# ETRX_Shield.net
KiCad netlist of a schematic drawn in Altium Designer
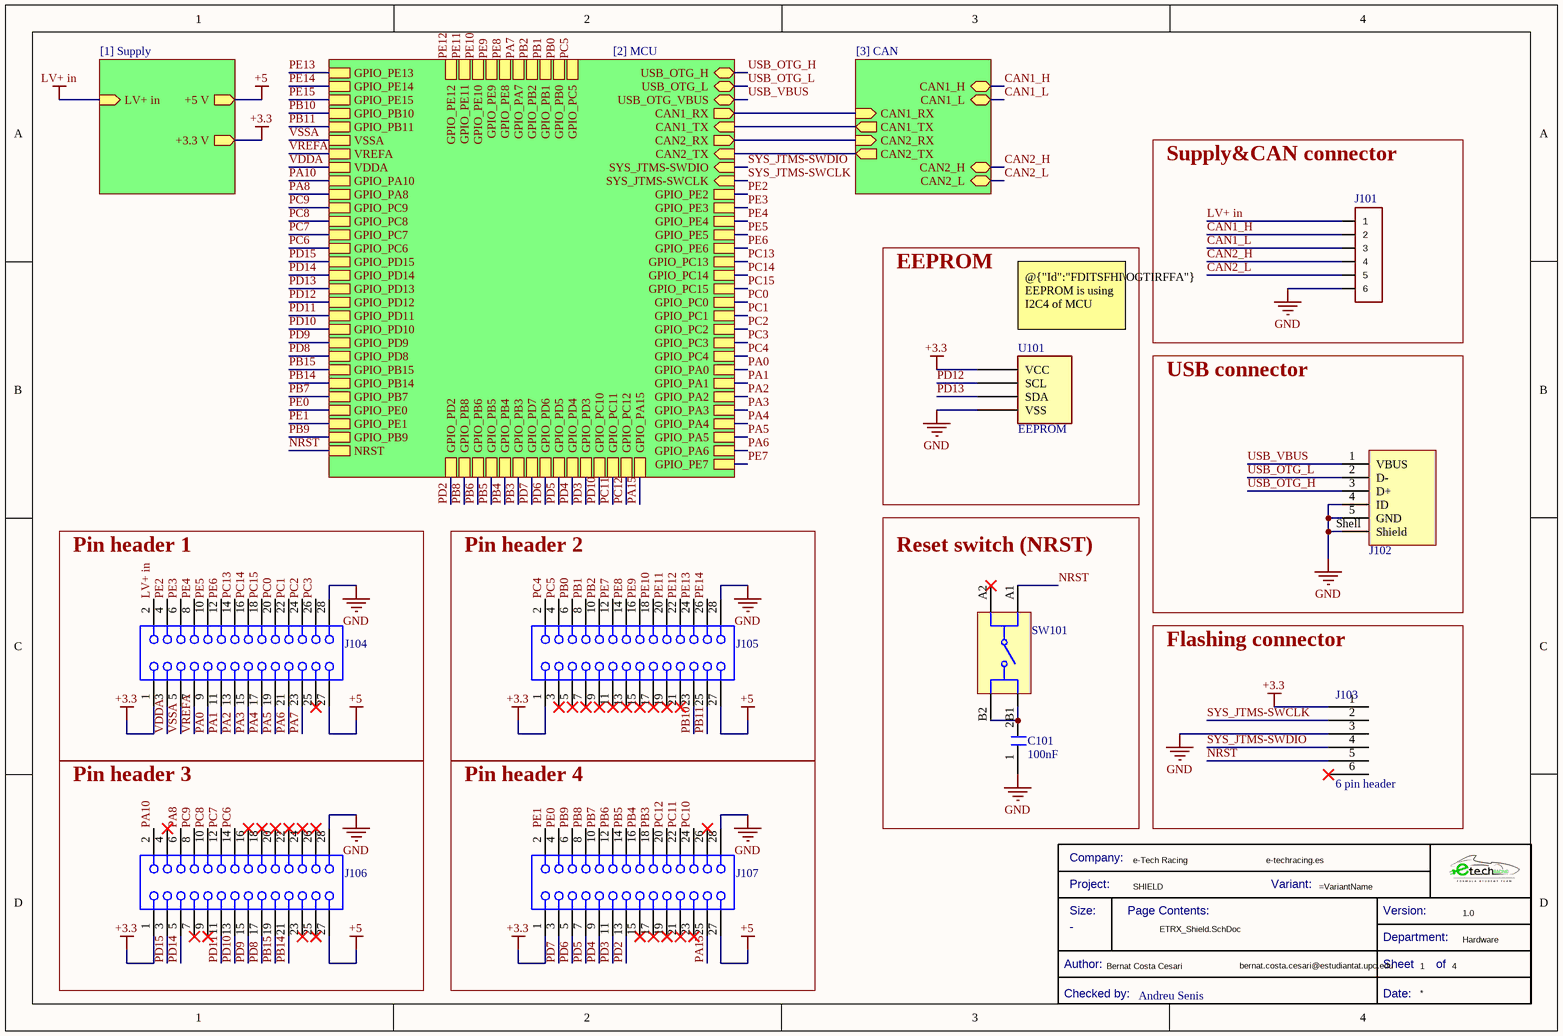
[diagram p0: ETRX_Shield.SchDoc]

(export (version "E")
  (design (tool "Eeschema 10.0.6"))
  (components
    (comp (ref "*")
      (value "Title Block_template")
      (description "Standard Title Block")
      (fields
        (field (name "SIZE") "-")
        (field (name ".CREATOR") "GP")
        (field (name ".PCBCHECK") "GP")
        (field (name ".SCHCHECK") "GP")
      )
      (libsource (lib "e-Tech_Racing") (part "Title Block_template"))
    )
    (comp (ref "C101")
      (value "885012208058")
      (footprint "C1206FNPC-RW")
      (description "Cap Cer 0.1UF 25V X7R 1206")
      (fields
        (field (name "MANUFACTURER") "Wurth Electronics")
        (field (name "TOLERANCE") "10%")
        (field (name "CAPACITANCE") "100nF")
        (field (name ".CREATOR") "DO")
      )
      (libsource (lib "Passives") (part "C100n-25V-1206FNPC-X7R"))
    )
    (comp (ref "J101")
      (value "LEMO Connector    6 pin EXG.0B.306.HLN Elbow receptacle for printed circuit (solder mount), Female Contact Drawing Rev. 00 Source: http://www.lemo.com/catalog/ROW/UK_English/unipole_multipole.pdf")
      (footprint "EXG.0B.306.HLN")
      (fields (field (name "MPN") "EXG.0B.306.HLN"))
      (libsource (lib "LEMO-EXG.0B.306.HLN") (part "EXG.0B.306.HLN"))
    )
    (comp (ref "J102")
      (value "629105136821")
      (footprint "629105136821")
      (description "WR-COM Micro USB 2.0 SMT Type B Horizontal 5 Contacts")
      (fields (field (name "MANUFACTURER") "Wurth Elektronik"))
      (libsource (lib "WR-USB") (part "629105136821"))
    )
    (comp (ref "J103") (value "6 pin header") (libsource (lib "CAN Transceiver") (part "6 pin header")))
    (comp (ref "J104")
      (value "62202821821")
      (footprint "62202821821")
      (description "WR-PHD Socket Header, THT, Vertical, pitch 1.27mm, 2 Row, 28P")
      (fields (field (name "MANUFACTURER") "Wurth Elektronik"))
      (libsource (lib "Altium_WR-PHD (rev22b)") (part "62202821821"))
    )
    (comp (ref "J105")
      (value "62202821821")
      (footprint "62202821821")
      (description "WR-PHD Socket Header, THT, Vertical, pitch 1.27mm, 2 Row, 28P")
      (fields (field (name "MANUFACTURER") "Wurth Elektronik"))
      (libsource (lib "Altium_WR-PHD (rev22b)") (part "62202821821"))
    )
    (comp (ref "J106")
      (value "62202821821")
      (footprint "62202821821")
      (description "WR-PHD Socket Header, THT, Vertical, pitch 1.27mm, 2 Row, 28P")
      (fields (field (name "MANUFACTURER") "Wurth Elektronik"))
      (libsource (lib "Altium_WR-PHD (rev22b)") (part "62202821821"))
    )
    (comp (ref "J107")
      (value "62202821821")
      (footprint "62202821821")
      (description "WR-PHD Socket Header, THT, Vertical, pitch 1.27mm, 2 Row, 28P")
      (fields (field (name "MANUFACTURER") "Wurth Elektronik"))
      (libsource (lib "Altium_WR-PHD (rev22b)") (part "62202821821"))
    )
    (comp (ref "SW101")
      (value "430773034825")
      (footprint "WS-TASV_L6W6H3.4_4307x30348xx")
      (description "WS-TASV J-Hook SMT Hermetic Tact Switch, L6 x W6 x H3.4mm, 250g, SPST-NO, 12V, 50mA")
      (fields (field (name "MANUFACTURER") "Wurth Elektronik"))
      (libsource (lib "Altium_WS-SW bo") (part "430773034825"))
    )
    (comp (ref "U101") (value "EEPROM") (libsource (lib "CAN Transceiver") (part "I2C_EEPROM")))
  )
  (nets
    (net (code "1") (name "+3.3") (class "Default")
      (node (ref "J103") (pin "1") (pinfunction "1_1") (pintype "passive"))
      (node (ref "J104") (pin "1") (pinfunction "1_1") (pintype "passive"))
      (node (ref "J105") (pin "1") (pinfunction "1_1") (pintype "passive"))
      (node (ref "J106") (pin "1") (pinfunction "1_1") (pintype "passive"))
      (node (ref "J107") (pin "1") (pinfunction "1_1") (pintype "passive"))
      (node (ref "U101") (pin "1") (pinfunction "VCC_1") (pintype "passive"))
    )
    (net (code "2") (name "+5") (class "Default")
      (node (ref "J104") (pin "27") (pinfunction "27_27") (pintype "passive"))
      (node (ref "J105") (pin "27") (pinfunction "27_27") (pintype "passive"))
      (node (ref "J106") (pin "27") (pinfunction "27_27") (pintype "passive"))
      (node (ref "J107") (pin "27") (pinfunction "27_27") (pintype "passive"))
    )
    (net (code "3") (name "/CAN1_H") (class "Default")
      (node (ref "J101") (pin "2") (pinfunction "2_2") (pintype "passive"))
    )
    (net (code "4") (name "/CAN1_L") (class "Default")
      (node (ref "J101") (pin "3") (pinfunction "3_3") (pintype "passive"))
    )
    (net (code "7") (name "/CAN2_H") (class "Default")
      (node (ref "J101") (pin "4") (pinfunction "4_4") (pintype "passive"))
    )
    (net (code "8") (name "/CAN2_L") (class "Default")
      (node (ref "J101") (pin "5") (pinfunction "5_5") (pintype "passive"))
    )
    (net (code "11") (name "/NRST") (class "Default")
      (node (ref "J103") (pin "5") (pinfunction "5_5") (pintype "passive"))
      (node (ref "SW101") (pin "A1") (pinfunction "A1_A1") (pintype "passive"))
    )
    (net (code "12") (name "/PA0") (class "Default")
      (node (ref "J104") (pin "9") (pinfunction "9_9") (pintype "passive"))
    )
    (net (code "13") (name "/PA1") (class "Default")
      (node (ref "J104") (pin "11") (pinfunction "11_11") (pintype "passive"))
    )
    (net (code "14") (name "/PA2") (class "Default")
      (node (ref "J104") (pin "13") (pinfunction "13_13") (pintype "passive"))
    )
    (net (code "15") (name "/PA3") (class "Default")
      (node (ref "J104") (pin "15") (pinfunction "15_15") (pintype "passive"))
    )
    (net (code "16") (name "/PA4") (class "Default")
      (node (ref "J104") (pin "17") (pinfunction "17_17") (pintype "passive"))
    )
    (net (code "17") (name "/PA5") (class "Default")
      (node (ref "J104") (pin "19") (pinfunction "19_19") (pintype "passive"))
    )
    (net (code "18") (name "/PA6") (class "Default")
      (node (ref "J104") (pin "21") (pinfunction "21_21") (pintype "passive"))
    )
    (net (code "19") (name "/PA7") (class "Default")
      (node (ref "J104") (pin "23") (pinfunction "23_23") (pintype "passive"))
    )
    (net (code "20") (name "/PA8") (class "Default")
      (node (ref "J106") (pin "6") (pinfunction "6_6") (pintype "passive"))
    )
    (net (code "21") (name "/PA10") (class "Default")
      (node (ref "J106") (pin "2") (pinfunction "2_2") (pintype "passive"))
    )
    (net (code "22") (name "/PA15") (class "Default")
      (node (ref "J107") (pin "25") (pinfunction "25_25") (pintype "passive"))
    )
    (net (code "23") (name "/PB0") (class "Default")
      (node (ref "J105") (pin "6") (pinfunction "6_6") (pintype "passive"))
    )
    (net (code "24") (name "/PB1") (class "Default")
      (node (ref "J105") (pin "8") (pinfunction "8_8") (pintype "passive"))
    )
    (net (code "25") (name "/PB2") (class "Default")
      (node (ref "J105") (pin "10") (pinfunction "10_10") (pintype "passive"))
    )
    (net (code "26") (name "/PB3") (class "Default")
      (node (ref "J107") (pin "18") (pinfunction "18_18") (pintype "passive"))
    )
    (net (code "27") (name "/PB4") (class "Default")
      (node (ref "J107") (pin "16") (pinfunction "16_16") (pintype "passive"))
    )
    (net (code "28") (name "/PB5") (class "Default")
      (node (ref "J107") (pin "14") (pinfunction "14_14") (pintype "passive"))
    )
    (net (code "29") (name "/PB6") (class "Default")
      (node (ref "J107") (pin "12") (pinfunction "12_12") (pintype "passive"))
    )
    (net (code "30") (name "/PB7") (class "Default")
      (node (ref "J107") (pin "10") (pinfunction "10_10") (pintype "passive"))
    )
    (net (code "31") (name "/PB8") (class "Default")
      (node (ref "J107") (pin "8") (pinfunction "8_8") (pintype "passive"))
    )
    (net (code "32") (name "/PB9") (class "Default")
      (node (ref "J107") (pin "6") (pinfunction "6_6") (pintype "passive"))
    )
    (net (code "33") (name "/PB10") (class "Default")
      (node (ref "J105") (pin "23") (pinfunction "23_23") (pintype "passive"))
    )
    (net (code "34") (name "/PB11") (class "Default")
      (node (ref "J105") (pin "25") (pinfunction "25_25") (pintype "passive"))
    )
    (net (code "35") (name "/PB14") (class "Default")
      (node (ref "J106") (pin "21") (pinfunction "21_21") (pintype "passive"))
    )
    (net (code "36") (name "/PB15") (class "Default")
      (node (ref "J106") (pin "19") (pinfunction "19_19") (pintype "passive"))
    )
    (net (code "37") (name "/PC0") (class "Default")
      (node (ref "J104") (pin "20") (pinfunction "20_20") (pintype "passive"))
    )
    (net (code "38") (name "/PC1") (class "Default")
      (node (ref "J104") (pin "22") (pinfunction "22_22") (pintype "passive"))
    )
    (net (code "39") (name "/PC2") (class "Default")
      (node (ref "J104") (pin "24") (pinfunction "24_24") (pintype "passive"))
    )
    (net (code "40") (name "/PC3") (class "Default")
      (node (ref "J104") (pin "26") (pinfunction "26_26") (pintype "passive"))
    )
    (net (code "41") (name "/PC4") (class "Default")
      (node (ref "J105") (pin "2") (pinfunction "2_2") (pintype "passive"))
    )
    (net (code "42") (name "/PC5") (class "Default")
      (node (ref "J105") (pin "4") (pinfunction "4_4") (pintype "passive"))
    )
    (net (code "43") (name "/PC6") (class "Default")
      (node (ref "J106") (pin "14") (pinfunction "14_14") (pintype "passive"))
    )
    (net (code "44") (name "/PC7") (class "Default")
      (node (ref "J106") (pin "12") (pinfunction "12_12") (pintype "passive"))
    )
    (net (code "45") (name "/PC8") (class "Default")
      (node (ref "J106") (pin "10") (pinfunction "10_10") (pintype "passive"))
    )
    (net (code "46") (name "/PC9") (class "Default")
      (node (ref "J106") (pin "8") (pinfunction "8_8") (pintype "passive"))
    )
    (net (code "47") (name "/PC10") (class "Default")
      (node (ref "J107") (pin "24") (pinfunction "24_24") (pintype "passive"))
    )
    (net (code "48") (name "/PC11") (class "Default")
      (node (ref "J107") (pin "22") (pinfunction "22_22") (pintype "passive"))
    )
    (net (code "49") (name "/PC12") (class "Default")
      (node (ref "J107") (pin "20") (pinfunction "20_20") (pintype "passive"))
    )
    (net (code "50") (name "/PC13") (class "Default")
      (node (ref "J104") (pin "14") (pinfunction "14_14") (pintype "passive"))
    )
    (net (code "51") (name "/PC14") (class "Default")
      (node (ref "J104") (pin "16") (pinfunction "16_16") (pintype "passive"))
    )
    (net (code "52") (name "/PC15") (class "Default")
      (node (ref "J104") (pin "18") (pinfunction "18_18") (pintype "passive"))
    )
    (net (code "53") (name "/PD2") (class "Default")
      (node (ref "J107") (pin "13") (pinfunction "13_13") (pintype "passive"))
    )
    (net (code "54") (name "/PD3") (class "Default")
      (node (ref "J107") (pin "11") (pinfunction "11_11") (pintype "passive"))
    )
    (net (code "55") (name "/PD4") (class "Default")
      (node (ref "J107") (pin "9") (pinfunction "9_9") (pintype "passive"))
    )
    (net (code "56") (name "/PD5") (class "Default")
      (node (ref "J107") (pin "7") (pinfunction "7_7") (pintype "passive"))
    )
    (net (code "57") (name "/PD6") (class "Default")
      (node (ref "J107") (pin "5") (pinfunction "5_5") (pintype "passive"))
    )
    (net (code "58") (name "/PD7") (class "Default")
      (node (ref "J107") (pin "3") (pinfunction "3_3") (pintype "passive"))
    )
    (net (code "59") (name "/PD8") (class "Default")
      (node (ref "J106") (pin "17") (pinfunction "17_17") (pintype "passive"))
    )
    (net (code "60") (name "/PD9") (class "Default")
      (node (ref "J106") (pin "15") (pinfunction "15_15") (pintype "passive"))
    )
    (net (code "61") (name "/PD10") (class "Default")
      (node (ref "J106") (pin "13") (pinfunction "13_13") (pintype "passive"))
    )
    (net (code "62") (name "/PD11") (class "Default")
      (node (ref "J106") (pin "11") (pinfunction "11_11") (pintype "passive"))
    )
    (net (code "63") (name "/PD12") (class "Default")
      (node (ref "U101") (pin "2") (pinfunction "SCL_2") (pintype "passive"))
    )
    (net (code "64") (name "/PD13") (class "Default")
      (node (ref "U101") (pin "3") (pinfunction "SDA_3") (pintype "passive"))
    )
    (net (code "65") (name "/PD14") (class "Default")
      (node (ref "J106") (pin "5") (pinfunction "5_5") (pintype "passive"))
    )
    (net (code "66") (name "/PD15") (class "Default")
      (node (ref "J106") (pin "3") (pinfunction "3_3") (pintype "passive"))
    )
    (net (code "67") (name "/PE0") (class "Default")
      (node (ref "J107") (pin "4") (pinfunction "4_4") (pintype "passive"))
    )
    (net (code "68") (name "/PE1") (class "Default")
      (node (ref "J107") (pin "2") (pinfunction "2_2") (pintype "passive"))
    )
    (net (code "69") (name "/PE2") (class "Default")
      (node (ref "J104") (pin "4") (pinfunction "4_4") (pintype "passive"))
    )
    (net (code "70") (name "/PE3") (class "Default")
      (node (ref "J104") (pin "6") (pinfunction "6_6") (pintype "passive"))
    )
    (net (code "71") (name "/PE4") (class "Default")
      (node (ref "J104") (pin "8") (pinfunction "8_8") (pintype "passive"))
    )
    (net (code "72") (name "/PE5") (class "Default")
      (node (ref "J104") (pin "10") (pinfunction "10_10") (pintype "passive"))
    )
    (net (code "73") (name "/PE6") (class "Default")
      (node (ref "J104") (pin "12") (pinfunction "12_12") (pintype "passive"))
    )
    (net (code "74") (name "/PE7") (class "Default")
      (node (ref "J105") (pin "12") (pinfunction "12_12") (pintype "passive"))
    )
    (net (code "75") (name "/PE8") (class "Default")
      (node (ref "J105") (pin "14") (pinfunction "14_14") (pintype "passive"))
    )
    (net (code "76") (name "/PE9") (class "Default")
      (node (ref "J105") (pin "16") (pinfunction "16_16") (pintype "passive"))
    )
    (net (code "77") (name "/PE10") (class "Default")
      (node (ref "J105") (pin "18") (pinfunction "18_18") (pintype "passive"))
    )
    (net (code "78") (name "/PE11") (class "Default")
      (node (ref "J105") (pin "20") (pinfunction "20_20") (pintype "passive"))
    )
    (net (code "79") (name "/PE12") (class "Default")
      (node (ref "J105") (pin "22") (pinfunction "22_22") (pintype "passive"))
    )
    (net (code "80") (name "/PE13") (class "Default")
      (node (ref "J105") (pin "24") (pinfunction "24_24") (pintype "passive"))
    )
    (net (code "81") (name "/PE14") (class "Default")
      (node (ref "J105") (pin "26") (pinfunction "26_26") (pintype "passive"))
    )
    (net (code "83") (name "/SYS_JTMS-SWCLK") (class "Default")
      (node (ref "J103") (pin "2") (pinfunction "2_2") (pintype "passive"))
    )
    (net (code "84") (name "/SYS_JTMS-SWDIO") (class "Default")
      (node (ref "J103") (pin "4") (pinfunction "4_4") (pintype "passive"))
    )
    (net (code "85") (name "/USB_OTG_H") (class "Default")
      (node (ref "J102") (pin "3") (pinfunction "D+_3") (pintype "passive"))
    )
    (net (code "86") (name "/USB_OTG_L") (class "Default")
      (node (ref "J102") (pin "2") (pinfunction "D-_2") (pintype "passive"))
    )
    (net (code "87") (name "/USB_VBUS") (class "Default")
      (node (ref "J102") (pin "1") (pinfunction "VBUS_1") (pintype "passive"))
    )
    (net (code "88") (name "/VDDA") (class "Default")
      (node (ref "J104") (pin "3") (pinfunction "3_3") (pintype "passive"))
    )
    (net (code "89") (name "/VREFA") (class "Default")
      (node (ref "J104") (pin "7") (pinfunction "7_7") (pintype "passive"))
    )
    (net (code "90") (name "/VSSA") (class "Default")
      (node (ref "J104") (pin "5") (pinfunction "5_5") (pintype "passive"))
    )
    (net (code "91") (name "GND") (class "Default")
      (node (ref "C101") (pin "1") (pinfunction "1_1") (pintype "passive"))
      (node (ref "J101") (pin "6") (pinfunction "6_6") (pintype "passive"))
      (node (ref "J102") (pin "4") (pinfunction "ID_4") (pintype "passive"))
      (node (ref "J102") (pin "5") (pinfunction "GND_5") (pintype "passive"))
      (node (ref "J102") (pin "Shell") (pinfunction "Shield_Shell") (pintype "passive"))
      (node (ref "J103") (pin "3") (pinfunction "3_3") (pintype "passive"))
      (node (ref "J104") (pin "28") (pinfunction "28_28") (pintype "passive"))
      (node (ref "J105") (pin "28") (pinfunction "28_28") (pintype "passive"))
      (node (ref "J106") (pin "28") (pinfunction "28_28") (pintype "passive"))
      (node (ref "J107") (pin "28") (pinfunction "28_28") (pintype "passive"))
      (node (ref "U101") (pin "4") (pinfunction "VSS_4") (pintype "power_in"))
    )
    (net (code "92") (name "LV+ in") (class "Default")
      (node (ref "J101") (pin "1") (pinfunction "1_1") (pintype "passive"))
      (node (ref "J104") (pin "2") (pinfunction "2_2") (pintype "passive"))
    )
    (net (code "93") (name "Net-(C101-Pad2)") (class "Default")
      (node (ref "C101") (pin "2") (pinfunction "2_2") (pintype "passive"))
      (node (ref "SW101") (pin "B1") (pinfunction "B1_B1") (pintype "passive"))
      (node (ref "SW101") (pin "B2") (pinfunction "B2_B2") (pintype "passive"))
    )
    (net (code "94") (name "unconnected-(J103-Pad6)") (class "Default")
      (node (ref "J103") (pin "6") (pinfunction "6_6") (pintype "passive+no_connect"))
    )
    (net (code "95") (name "unconnected-(J104-Pad25)") (class "Default")
      (node (ref "J104") (pin "25") (pinfunction "25_25") (pintype "passive+no_connect"))
    )
    (net (code "96") (name "unconnected-(J105-Pad3)") (class "Default")
      (node (ref "J105") (pin "3") (pinfunction "3_3") (pintype "passive+no_connect"))
    )
    (net (code "97") (name "unconnected-(J105-Pad5)") (class "Default")
      (node (ref "J105") (pin "5") (pinfunction "5_5") (pintype "passive+no_connect"))
    )
    (net (code "98") (name "unconnected-(J105-Pad7)") (class "Default")
      (node (ref "J105") (pin "7") (pinfunction "7_7") (pintype "passive+no_connect"))
    )
    (net (code "99") (name "unconnected-(J105-Pad9)") (class "Default")
      (node (ref "J105") (pin "9") (pinfunction "9_9") (pintype "passive+no_connect"))
    )
    (net (code "100") (name "unconnected-(J105-Pad11)") (class "Default")
      (node (ref "J105") (pin "11") (pinfunction "11_11") (pintype "passive+no_connect"))
    )
    (net (code "101") (name "unconnected-(J105-Pad13)") (class "Default")
      (node (ref "J105") (pin "13") (pinfunction "13_13") (pintype "passive+no_connect"))
    )
    (net (code "102") (name "unconnected-(J105-Pad15)") (class "Default")
      (node (ref "J105") (pin "15") (pinfunction "15_15") (pintype "passive+no_connect"))
    )
    (net (code "103") (name "unconnected-(J105-Pad17)") (class "Default")
      (node (ref "J105") (pin "17") (pinfunction "17_17") (pintype "passive+no_connect"))
    )
    (net (code "104") (name "unconnected-(J105-Pad19)") (class "Default")
      (node (ref "J105") (pin "19") (pinfunction "19_19") (pintype "passive+no_connect"))
    )
    (net (code "105") (name "unconnected-(J105-Pad21)") (class "Default")
      (node (ref "J105") (pin "21") (pinfunction "21_21") (pintype "passive+no_connect"))
    )
    (net (code "106") (name "unconnected-(J106-Pad4)") (class "Default")
      (node (ref "J106") (pin "4") (pinfunction "4_4") (pintype "passive+no_connect"))
    )
    (net (code "107") (name "unconnected-(J106-Pad7)") (class "Default")
      (node (ref "J106") (pin "7") (pinfunction "7_7") (pintype "passive+no_connect"))
    )
    (net (code "108") (name "unconnected-(J106-Pad9)") (class "Default")
      (node (ref "J106") (pin "9") (pinfunction "9_9") (pintype "passive+no_connect"))
    )
    (net (code "109") (name "unconnected-(J106-Pad16)") (class "Default")
      (node (ref "J106") (pin "16") (pinfunction "16_16") (pintype "passive+no_connect"))
    )
    (net (code "110") (name "unconnected-(J106-Pad18)") (class "Default")
      (node (ref "J106") (pin "18") (pinfunction "18_18") (pintype "passive+no_connect"))
    )
    (net (code "111") (name "unconnected-(J106-Pad20)") (class "Default")
      (node (ref "J106") (pin "20") (pinfunction "20_20") (pintype "passive+no_connect"))
    )
    (net (code "112") (name "unconnected-(J106-Pad22)") (class "Default")
      (node (ref "J106") (pin "22") (pinfunction "22_22") (pintype "passive+no_connect"))
    )
    (net (code "113") (name "unconnected-(J106-Pad23)") (class "Default")
      (node (ref "J106") (pin "23") (pinfunction "23_23") (pintype "passive+no_connect"))
    )
    (net (code "114") (name "unconnected-(J106-Pad24)") (class "Default")
      (node (ref "J106") (pin "24") (pinfunction "24_24") (pintype "passive+no_connect"))
    )
    (net (code "115") (name "unconnected-(J106-Pad25)") (class "Default")
      (node (ref "J106") (pin "25") (pinfunction "25_25") (pintype "passive+no_connect"))
    )
    (net (code "116") (name "unconnected-(J106-Pad26)") (class "Default")
      (node (ref "J106") (pin "26") (pinfunction "26_26") (pintype "passive+no_connect"))
    )
    (net (code "117") (name "unconnected-(J107-Pad15)") (class "Default")
      (node (ref "J107") (pin "15") (pinfunction "15_15") (pintype "passive+no_connect"))
    )
    (net (code "118") (name "unconnected-(J107-Pad17)") (class "Default")
      (node (ref "J107") (pin "17") (pinfunction "17_17") (pintype "passive+no_connect"))
    )
    (net (code "119") (name "unconnected-(J107-Pad19)") (class "Default")
      (node (ref "J107") (pin "19") (pinfunction "19_19") (pintype "passive+no_connect"))
    )
    (net (code "120") (name "unconnected-(J107-Pad21)") (class "Default")
      (node (ref "J107") (pin "21") (pinfunction "21_21") (pintype "passive+no_connect"))
    )
    (net (code "121") (name "unconnected-(J107-Pad23)") (class "Default")
      (node (ref "J107") (pin "23") (pinfunction "23_23") (pintype "passive+no_connect"))
    )
    (net (code "122") (name "unconnected-(J107-Pad26)") (class "Default")
      (node (ref "J107") (pin "26") (pinfunction "26_26") (pintype "passive+no_connect"))
    )
    (net (code "123") (name "unconnected-(SW101-PadA2)") (class "Default")
      (node (ref "SW101") (pin "A2") (pinfunction "A2_A2") (pintype "passive+no_connect"))
    )
  )
)
